# LitVP-V3.net
KiCad netlist of a schematic drawn in Altium Designer
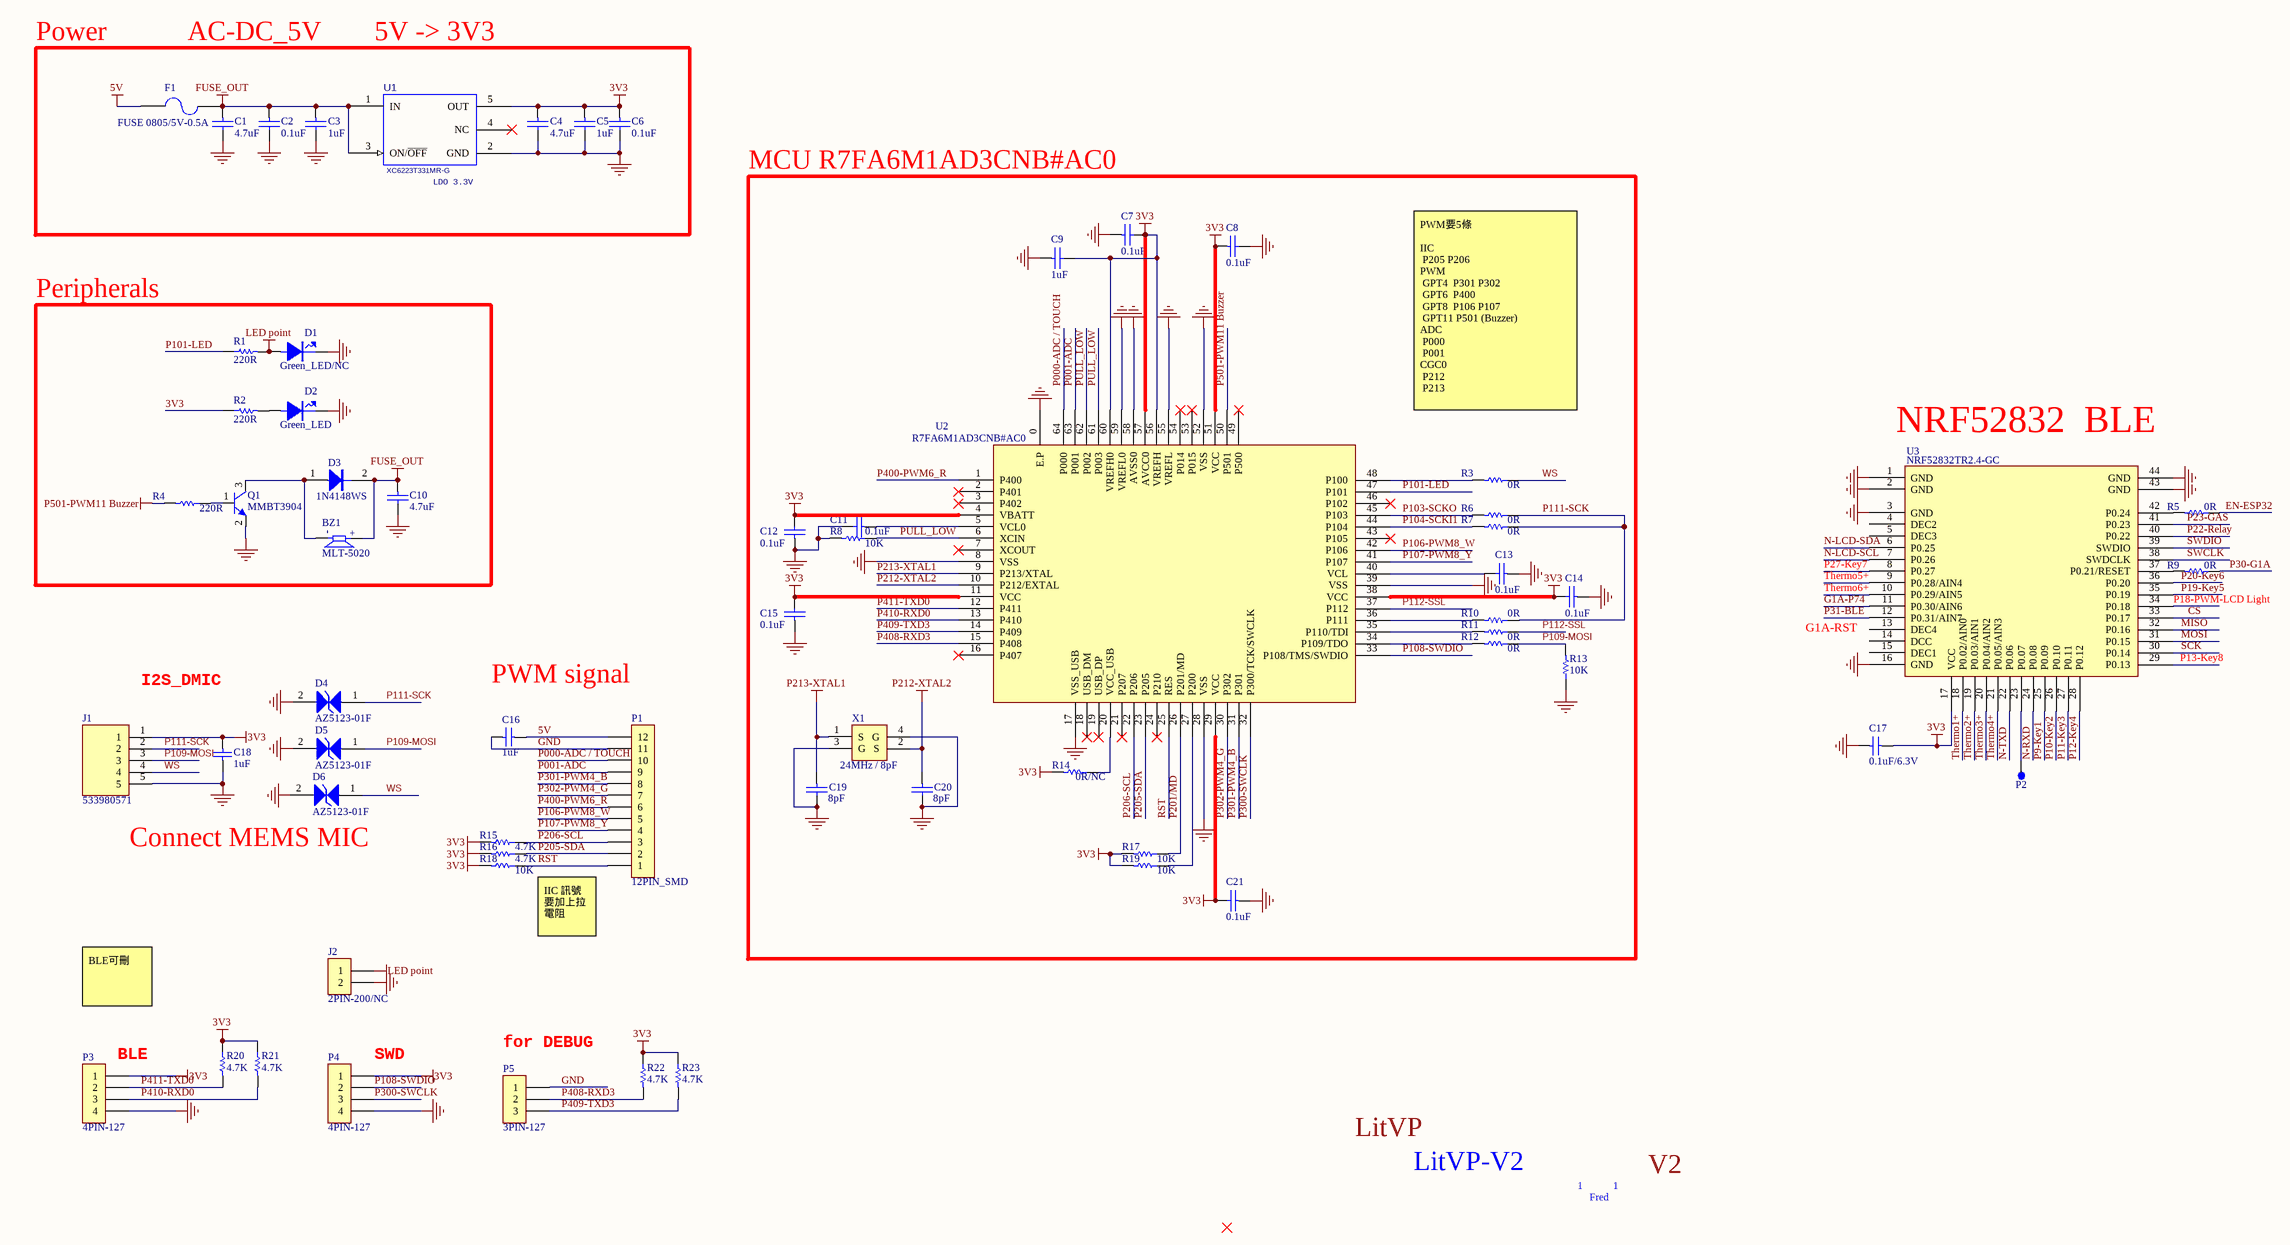
[diagram p0: LitVP-V3.SchDoc]

(export (version "E")
  (design (tool "Eeschema 10.0.6"))
  (components
    (comp (ref "BZ1")
      (value "MLT-5020")
      (footprint "BUZZER-SMD-5*5mm")
      (description "Buzzer")
      (libsource (lib "*") (part "YZ5020CS-03L-4.0-12-R"))
    )
    (comp (ref "C1")
      (value "4.7uF")
      (footprint "QUAN:0402C")
      (description "Capacitor")
      (libsource (lib "CAP") (part "CAP"))
    )
    (comp (ref "C2")
      (value "0.1uF")
      (footprint "QUAN:0402C")
      (description "Capacitor")
      (libsource (lib "CAP") (part "CAP"))
    )
    (comp (ref "C3")
      (value "1uF")
      (footprint "QUAN:0402C")
      (description "Capacitor")
      (libsource (lib "CAP") (part "CAP"))
    )
    (comp (ref "C4")
      (value "4.7uF")
      (footprint "QUAN:0402C")
      (description "Capacitor")
      (libsource (lib "CAP") (part "CAP"))
    )
    (comp (ref "C5")
      (value "1uF")
      (footprint "QUAN:0402C")
      (description "Capacitor")
      (libsource (lib "CAP") (part "CAP"))
    )
    (comp (ref "C6")
      (value "0.1uF")
      (footprint "QUAN:0402C")
      (description "Capacitor")
      (libsource (lib "CAP") (part "CAP"))
    )
    (comp (ref "C7")
      (value "0.1uF")
      (footprint "QUAN:0402C")
      (description "Capacitor")
      (libsource (lib "CAP") (part "CAP"))
    )
    (comp (ref "C8")
      (value "0.1uF")
      (footprint "QUAN:0402C")
      (description "Capacitor")
      (libsource (lib "CAP") (part "CAP"))
    )
    (comp (ref "C9")
      (value "1uF")
      (footprint "QUAN:0402C")
      (description "Capacitor")
      (libsource (lib "CAP") (part "CAP"))
    )
    (comp (ref "C10")
      (value "4.7uF")
      (footprint "QUAN:0402C")
      (description "Capacitor")
      (libsource (lib "CAP") (part "CAP"))
    )
    (comp (ref "C11")
      (value "0.1uF")
      (footprint "QUAN:0402C")
      (description "Capacitor")
      (libsource (lib "CAP") (part "CAP"))
    )
    (comp (ref "C12")
      (value "0.1uF")
      (footprint "QUAN:0402C")
      (description "Capacitor")
      (libsource (lib "CAP") (part "CAP"))
    )
    (comp (ref "C13")
      (value "0.1uF")
      (footprint "QUAN:0402C")
      (description "Capacitor")
      (libsource (lib "CAP") (part "CAP"))
    )
    (comp (ref "C14")
      (value "0.1uF")
      (footprint "QUAN:0402C")
      (description "Capacitor")
      (libsource (lib "CAP") (part "CAP"))
    )
    (comp (ref "C15")
      (value "0.1uF")
      (footprint "QUAN:0402C")
      (description "Capacitor")
      (libsource (lib "CAP") (part "CAP"))
    )
    (comp (ref "C16")
      (value "1uF")
      (footprint "QUAN:0402C")
      (description "Capacitor")
      (libsource (lib "*") (part "Cap Semi"))
    )
    (comp (ref "C17")
      (value "0.1uF/6.3V")
      (footprint "0402C")
      (description "Capacitor (Semiconductor SIM Model)")
      (fields (field (name "PUBLISHER") "Altium Limited"))
      (libsource (lib "*") (part "Cap Semi"))
    )
    (comp (ref "C18")
      (value "1uF")
      (footprint "QUAN:0402C")
      (description "Capacitor")
      (libsource (lib "*") (part "Cap Semi"))
    )
    (comp (ref "C19")
      (value "8pF")
      (footprint "QUAN:0402C")
      (description "Capacitor")
      (libsource (lib "*") (part "CAP"))
    )
    (comp (ref "C20")
      (value "8pF")
      (footprint "QUAN:0402C")
      (description "Capacitor")
      (libsource (lib "*") (part "CAP"))
    )
    (comp (ref "C21")
      (value "0.1uF")
      (footprint "QUAN:0402C")
      (description "Capacitor")
      (libsource (lib "CAP") (part "CAP"))
    )
    (comp (ref "D1")
      (value "Green_LED/NC")
      (footprint "LED0603--0.4mm")
      (fields
        (field (name "MANUFACTURER'S PART NUMBER") "CL-170G-CD-T")
        (field (name "PART NUMBER") "41100017000")
        (field (name "MANUFACTURER") "Citizen")
      )
      (libsource (lib "*") (part "LED"))
    )
    (comp (ref "D2")
      (value "Green_LED")
      (footprint "LED0603--0.4mm")
      (fields
        (field (name "MANUFACTURER'S PART NUMBER") "CL-170G-CD-T")
        (field (name "PART NUMBER") "41100017000")
        (field (name "MANUFACTURER") "Citizen")
      )
      (libsource (lib "*") (part "LED"))
    )
    (comp (ref "D3")
      (value "1N4148WS")
      (footprint "SOD323-1N4148WS - pig pad")
      (libsource (lib "*") (part "DIODE"))
    )
    (comp (ref "D4")
      (value "AZ5123-01F")
      (footprint "LitVP-02:DIODE-0402")
      (description "ESD")
      (libsource (lib "*") (part "PESD5V0L1BA"))
    )
    (comp (ref "D5")
      (value "AZ5123-01F")
      (footprint "DIODE-0402")
      (description "ESD")
      (libsource (lib "*") (part "PESD5V0L1BA"))
    )
    (comp (ref "D6")
      (value "AZ5123-01F")
      (footprint "DIODE-0402")
      (description "ESD")
      (libsource (lib "*") (part "PESD5V0L1BA"))
    )
    (comp (ref "F1")
      (value "FUSE 0805/5V-0.5A")
      (footprint "QUAN:0805_FUSE")
      (description "Fuse")
      (libsource (lib "*") (part "FUSE2"))
    )
    (comp (ref "J1")
      (value "533980571")
      (footprint "SamacSys:53398-0571")
      (description "Connector")
      (fields (field (name "MANUFACTURER_PART_NUMBER") "53048-0510"))
      (libsource (lib "*") (part "53048-0510"))
    )
    (comp (ref "J2")
      (value "2PIN-200/NC")
      (footprint "2PIN-127")
      (description "Connector")
      (libsource (lib "PIN") (part "2PIN-200"))
    )
    (comp (ref "P1")
      (value "12PIN_SMD")
      (footprint "QUAN:12PIN_SAMTEC-MMT-136-02-X-SH")
      (libsource (lib "PIN") (part "12PIN_SMD"))
    )
    (comp (ref "P2") (value "TP") (footprint "TESTPAD-1X0.6MM-1") (libsource (lib "*") (part "TP")))
    (comp (ref "P3")
      (value "4PIN-127")
      (footprint "QUAN:4PIN-127_0.85_0.505")
      (description "1.27mm Header")
      (libsource (lib "*") (part "CON4"))
    )
    (comp (ref "P4")
      (value "4PIN-127")
      (footprint "QUAN:4PIN-127_0.85_0.505")
      (description "1.27mm Header")
      (libsource (lib "*") (part "CON4"))
    )
    (comp (ref "P5") (value "3PIN-127") (footprint "QUAN:3PIN-127") (libsource (lib "PIN") (part "3PIN-127")))
    (comp (ref "Q1")
      (value "MMBT3904")
      (footprint "QUAN:SOT-23")
      (description "NPN General Purpose Amplifier")
      (fields (field (name "PUBLISHER") "*"))
      (libsource (lib "*") (part "NPN-3"))
    )
    (comp (ref "R1")
      (value "220R")
      (footprint "QUAN:0402")
      (description "Resistor")
      (libsource (lib "*") (part "Res Semi"))
    )
    (comp (ref "R2")
      (value "220R")
      (footprint "QUAN:0402")
      (description "Resistor")
      (libsource (lib "*") (part "Res Semi"))
    )
    (comp (ref "R3")
      (value "0R")
      (footprint "QUAN:0402")
      (description "Resistor")
      (libsource (lib "*") (part "Res Semi"))
    )
    (comp (ref "R4")
      (value "220R")
      (footprint "QUAN:0402")
      (description "Resistor")
      (libsource (lib "*") (part "Res Semi"))
    )
    (comp (ref "R5")
      (value "0R")
      (footprint "0402")
      (description "Semiconductor Resistor")
      (fields (field (name "PUBLISHER") "Altium Limited"))
      (libsource (lib "*") (part "Res Semi"))
    )
    (comp (ref "R6")
      (value "0R")
      (footprint "QUAN:0402")
      (description "Resistor")
      (libsource (lib "*") (part "Res Semi"))
    )
    (comp (ref "R7")
      (value "0R")
      (footprint "QUAN:0402")
      (description "Resistor")
      (libsource (lib "*") (part "Res Semi"))
    )
    (comp (ref "R8")
      (value "10K")
      (footprint "QUAN:0402")
      (description "Resistor")
      (libsource (lib "*") (part "Res Semi"))
    )
    (comp (ref "R9")
      (value "0R")
      (footprint "0402")
      (description "Semiconductor Resistor")
      (fields (field (name "PUBLISHER") "Altium Limited"))
      (libsource (lib "*") (part "Res Semi"))
    )
    (comp (ref "R10")
      (value "0R")
      (footprint "QUAN:0402")
      (description "Resistor")
      (libsource (lib "*") (part "Res Semi"))
    )
    (comp (ref "R11")
      (value "0R")
      (footprint "QUAN:0402")
      (description "Resistor")
      (libsource (lib "*") (part "Res Semi"))
    )
    (comp (ref "R12")
      (value "0R")
      (footprint "QUAN:0402")
      (description "Resistor")
      (libsource (lib "*") (part "Res Semi"))
    )
    (comp (ref "R13")
      (value "10K")
      (footprint "QUAN:0402")
      (description "Resistor")
      (libsource (lib "*") (part "Res Semi"))
    )
    (comp (ref "R14")
      (value "0R/NC")
      (footprint "QUAN:0402")
      (description "Resistor")
      (libsource (lib "*") (part "Res Semi"))
    )
    (comp (ref "R15")
      (value "4.7K")
      (footprint "QUAN:0402")
      (description "Resistor")
      (libsource (lib "*") (part "Res Semi"))
    )
    (comp (ref "R16")
      (value "4.7K")
      (footprint "QUAN:0402")
      (description "Resistor")
      (libsource (lib "*") (part "Res Semi"))
    )
    (comp (ref "R17")
      (value "10K")
      (footprint "QUAN:0402")
      (description "Resistor")
      (libsource (lib "*") (part "Res Semi"))
    )
    (comp (ref "R18")
      (value "10K")
      (footprint "QUAN:0402")
      (description "Resistor")
      (libsource (lib "*") (part "Res Semi"))
    )
    (comp (ref "R19")
      (value "10K")
      (footprint "QUAN:0402")
      (description "Resistor")
      (libsource (lib "*") (part "Res Semi"))
    )
    (comp (ref "R20")
      (value "4.7K")
      (footprint "QUAN:0402")
      (description "Resistor")
      (libsource (lib "*") (part "Res Semi"))
    )
    (comp (ref "R21")
      (value "4.7K")
      (footprint "QUAN:0402")
      (description "Resistor")
      (libsource (lib "*") (part "Res Semi"))
    )
    (comp (ref "R22")
      (value "4.7K")
      (footprint "QUAN:0402")
      (description "Resistor")
      (libsource (lib "*") (part "Res Semi"))
    )
    (comp (ref "R23")
      (value "4.7K")
      (footprint "QUAN:0402")
      (description "Resistor")
      (libsource (lib "*") (part "Res Semi"))
    )
    (comp (ref "U1")
      (value "XC6223T331MR-G")
      (footprint "SOT-23-5-0.95MM")
      (libsource (lib "*") (part "XC6223T331MR-G"))
    )
    (comp (ref "U2")
      (value "R7FA6M1AD3CNB#AC0")
      (footprint "QFN64-0.4mm-8X8")
      (description "MCU")
      (libsource (lib "*") (part "R7FA6M1AD3CNB#AC0"))
    )
    (comp (ref "U3")
      (value "NRF52832TR2.4-GC")
      (footprint "NRF52832TR2.4-GC")
      (libsource (lib "*") (part "NRF52832TR2.4-GC"))
    )
    (comp (ref "X1")
      (value "24MHz / 8pF")
      (footprint "XTAL-SMD-20X16")
      (libsource (lib "*") (part "XTAL-SMD-25*32"))
    )
  )
  (nets
    (net (code "1") (name "/CS") (class "Default")
      (node (ref "U3") (pin "33") (pinfunction "P0.17_33") (pintype "passive"))
    )
    (net (code "2") (name "/EN-ESP32") (class "Default")
      (node (ref "R5") (pin "1") (pinfunction "1_1") (pintype "passive"))
    )
    (net (code "3") (name "/G1A-P74") (class "Default")
      (node (ref "U3") (pin "11") (pinfunction "P0.30/AIN6_11") (pintype "passive"))
    )
    (net (code "4") (name "/MISO") (class "Default")
      (node (ref "U3") (pin "32") (pinfunction "P0.16_32") (pintype "passive"))
    )
    (net (code "5") (name "/MOSI") (class "Default")
      (node (ref "U3") (pin "31") (pinfunction "P0.15_31") (pintype "passive"))
    )
    (net (code "6") (name "/N-LCD-SCL") (class "Default")
      (node (ref "U3") (pin "7") (pinfunction "P0.26_7") (pintype "passive"))
    )
    (net (code "7") (name "/N-LCD-SDA") (class "Default")
      (node (ref "U3") (pin "6") (pinfunction "P0.25_6") (pintype "passive"))
    )
    (net (code "8") (name "/N-RXD") (class "Default")
      (node (ref "U3") (pin "24") (pinfunction "P0.08_24") (pintype "passive"))
    )
    (net (code "9") (name "/N-TXD") (class "Default")
      (node (ref "U3") (pin "22") (pinfunction "P0.06_22") (pintype "passive"))
    )
    (net (code "10") (name "/P000-ADC {slash} TOUCH") (class "Default")
      (node (ref "P1") (pin "10") (pinfunction "10_10") (pintype "passive"))
      (node (ref "U2") (pin "64") (pinfunction "P000_64") (pintype "passive"))
    )
    (net (code "11") (name "/P001-ADC") (class "Default")
      (node (ref "P1") (pin "9") (pinfunction "9_9") (pintype "passive"))
      (node (ref "U2") (pin "63") (pinfunction "P001_63") (pintype "passive"))
    )
    (net (code "12") (name "/P9-Key1") (class "Default")
      (node (ref "U3") (pin "25") (pinfunction "P0.09_25") (pintype "passive"))
    )
    (net (code "13") (name "/P10-Key2") (class "Default")
      (node (ref "U3") (pin "26") (pinfunction "P0.10_26") (pintype "passive"))
    )
    (net (code "14") (name "/P11-Key3") (class "Default")
      (node (ref "U3") (pin "27") (pinfunction "P0.11_27") (pintype "passive"))
    )
    (net (code "15") (name "/P12-Key4") (class "Default")
      (node (ref "U3") (pin "28") (pinfunction "P0.12_28") (pintype "passive"))
    )
    (net (code "16") (name "/P13-Key8") (class "Default")
      (node (ref "U3") (pin "29") (pinfunction "P0.13_29") (pintype "passive"))
    )
    (net (code "17") (name "/P18-PWM-LCD Light") (class "Default")
      (node (ref "U3") (pin "34") (pinfunction "P0.18_34") (pintype "passive"))
    )
    (net (code "18") (name "/P19-Key5") (class "Default")
      (node (ref "U3") (pin "35") (pinfunction "P0.19_35") (pintype "passive"))
    )
    (net (code "19") (name "/P20-Key6") (class "Default")
      (node (ref "U3") (pin "36") (pinfunction "P0.20_36") (pintype "passive"))
    )
    (net (code "20") (name "/P22-Relay") (class "Default")
      (node (ref "U3") (pin "40") (pinfunction "P0.22_40") (pintype "passive"))
    )
    (net (code "21") (name "/P23-GAS") (class "Default")
      (node (ref "U3") (pin "41") (pinfunction "P0.23_41") (pintype "passive"))
    )
    (net (code "22") (name "/P27-Key7") (class "Default")
      (node (ref "U3") (pin "8") (pinfunction "P0.27_8") (pintype "passive"))
    )
    (net (code "23") (name "/P30-G1A") (class "Default")
      (node (ref "R9") (pin "1") (pinfunction "1_1") (pintype "passive"))
    )
    (net (code "24") (name "/P31-BLE") (class "Default")
      (node (ref "U3") (pin "12") (pinfunction "P0.31/AIN7_12") (pintype "passive"))
    )
    (net (code "25") (name "/P101-LED") (class "Default")
      (node (ref "R1") (pin "1") (pinfunction "1_1") (pintype "passive"))
      (node (ref "U2") (pin "47") (pinfunction "P101_47") (pintype "passive"))
    )
    (net (code "26") (name "/P103-SCKO") (class "Default")
      (node (ref "R6") (pin "2") (pinfunction "2_2") (pintype "passive"))
      (node (ref "U2") (pin "45") (pinfunction "P103_45") (pintype "passive"))
    )
    (net (code "27") (name "/P104-SCKI1") (class "Default")
      (node (ref "R7") (pin "2") (pinfunction "2_2") (pintype "passive"))
      (node (ref "U2") (pin "44") (pinfunction "P104_44") (pintype "passive"))
    )
    (net (code "28") (name "/P106-PWM8_W") (class "Default")
      (node (ref "P1") (pin "5") (pinfunction "5_5") (pintype "passive"))
      (node (ref "U2") (pin "42") (pinfunction "P106_42") (pintype "passive"))
    )
    (net (code "29") (name "/P107-PWM8_Y") (class "Default")
      (node (ref "P1") (pin "4") (pinfunction "4_4") (pintype "passive"))
      (node (ref "U2") (pin "41") (pinfunction "P107_41") (pintype "passive"))
    )
    (net (code "30") (name "/P108-SWDIO") (class "Default")
      (node (ref "P4") (pin "2") (pinfunction "2_2") (pintype "passive"))
      (node (ref "U2") (pin "33") (pinfunction "P108/TMS/SWDIO_33") (pintype "passive"))
    )
    (net (code "31") (name "/P109-MOSI") (class "Default")
      (node (ref "D5") (pin "1") (pinfunction "1_1") (pintype "passive"))
      (node (ref "J1") (pin "3") (pinfunction "3_3") (pintype "passive"))
      (node (ref "R12") (pin "1") (pinfunction "1_1") (pintype "passive"))
      (node (ref "R13") (pin "2") (pinfunction "2_2") (pintype "passive"))
    )
    (net (code "32") (name "/P111-SCK") (class "Default")
      (node (ref "D4") (pin "1") (pinfunction "1_1") (pintype "passive"))
      (node (ref "J1") (pin "2") (pinfunction "2_2") (pintype "passive"))
      (node (ref "R10") (pin "1") (pinfunction "1_1") (pintype "passive"))
      (node (ref "R6") (pin "1") (pinfunction "1_1") (pintype "passive"))
      (node (ref "R7") (pin "1") (pinfunction "1_1") (pintype "passive"))
    )
    (net (code "33") (name "/P112-SSL") (class "Default")
      (node (ref "R11") (pin "1") (pinfunction "1_1") (pintype "passive"))
      (node (ref "U2") (pin "37") (pinfunction "P112_37") (pintype "passive"))
    )
    (net (code "34") (name "/P201{slash}MD") (class "Default")
      (node (ref "R17") (pin "1") (pinfunction "1_1") (pintype "passive"))
      (node (ref "U2") (pin "26") (pinfunction "P201/MD_26") (pintype "passive"))
    )
    (net (code "35") (name "/P205-SDA") (class "Default")
      (node (ref "P1") (pin "2") (pinfunction "2_2") (pintype "passive"))
      (node (ref "R16") (pin "1") (pinfunction "1_1") (pintype "passive"))
      (node (ref "U2") (pin "23") (pinfunction "P205_23") (pintype "passive"))
    )
    (net (code "36") (name "/P206-SCL") (class "Default")
      (node (ref "P1") (pin "3") (pinfunction "3_3") (pintype "passive"))
      (node (ref "R15") (pin "1") (pinfunction "1_1") (pintype "passive"))
      (node (ref "U2") (pin "22") (pinfunction "P206_22") (pintype "passive"))
    )
    (net (code "37") (name "/P300-SWCLK") (class "Default")
      (node (ref "P4") (pin "3") (pinfunction "3_3") (pintype "passive"))
      (node (ref "U2") (pin "32") (pinfunction "P300/TCK/SWCLK_32") (pintype "passive"))
    )
    (net (code "38") (name "/P301-PWM4_B") (class "Default")
      (node (ref "P1") (pin "8") (pinfunction "8_8") (pintype "passive"))
      (node (ref "U2") (pin "31") (pinfunction "P301_31") (pintype "passive"))
    )
    (net (code "39") (name "/P302-PWM4_G") (class "Default")
      (node (ref "P1") (pin "7") (pinfunction "7_7") (pintype "passive"))
      (node (ref "U2") (pin "30") (pinfunction "P302_30") (pintype "passive"))
    )
    (net (code "40") (name "/P400-PWM6_R") (class "Default")
      (node (ref "P1") (pin "6") (pinfunction "6_6") (pintype "passive"))
      (node (ref "U2") (pin "1") (pinfunction "P400_1") (pintype "passive"))
    )
    (net (code "41") (name "/P408-RXD3") (class "Default")
      (node (ref "P5") (pin "2") (pinfunction "2_2") (pintype "passive"))
      (node (ref "R22") (pin "2") (pinfunction "2_2") (pintype "passive"))
      (node (ref "U2") (pin "15") (pinfunction "P408_15") (pintype "passive"))
    )
    (net (code "42") (name "/P409-TXD3") (class "Default")
      (node (ref "P5") (pin "3") (pinfunction "3_3") (pintype "passive"))
      (node (ref "R23") (pin "2") (pinfunction "2_2") (pintype "passive"))
      (node (ref "U2") (pin "14") (pinfunction "P409_14") (pintype "passive"))
    )
    (net (code "43") (name "/P410-RXD0") (class "Default")
      (node (ref "P3") (pin "3") (pinfunction "3_3") (pintype "passive"))
      (node (ref "R21") (pin "2") (pinfunction "2_2") (pintype "passive"))
      (node (ref "U2") (pin "13") (pinfunction "P410_13") (pintype "passive"))
    )
    (net (code "44") (name "/P411-TXD0") (class "Default")
      (node (ref "P3") (pin "2") (pinfunction "2_2") (pintype "passive"))
      (node (ref "R20") (pin "2") (pinfunction "2_2") (pintype "passive"))
      (node (ref "U2") (pin "12") (pinfunction "P411_12") (pintype "passive"))
    )
    (net (code "45") (name "/PULL_LOW") (class "Default")
      (node (ref "R8") (pin "1") (pinfunction "1_1") (pintype "passive"))
      (node (ref "U2") (pin "6") (pinfunction "XCIN_6") (pintype "passive"))
      (node (ref "U2") (pin "61") (pinfunction "P003_61") (pintype "passive"))
      (node (ref "U2") (pin "62") (pinfunction "P002_62") (pintype "passive"))
    )
    (net (code "46") (name "/RST") (class "Default")
      (node (ref "P1") (pin "1") (pinfunction "1_1") (pintype "passive"))
      (node (ref "R18") (pin "1") (pinfunction "1_1") (pintype "passive"))
      (node (ref "U2") (pin "25") (pinfunction "RES_25") (pintype "passive"))
    )
    (net (code "47") (name "/SCK") (class "Default")
      (node (ref "U3") (pin "30") (pinfunction "P0.14_30") (pintype "passive"))
    )
    (net (code "48") (name "/SWCLK") (class "Default")
      (node (ref "U3") (pin "38") (pinfunction "SWDCLK_38") (pintype "passive"))
    )
    (net (code "49") (name "/SWDIO") (class "Default")
      (node (ref "U3") (pin "39") (pinfunction "SWDIO_39") (pintype "passive"))
    )
    (net (code "50") (name "/Thermo1+") (class "Default")
      (node (ref "U3") (pin "18") (pinfunction "P0.02/AIN0_18") (pintype "passive"))
    )
    (net (code "51") (name "/Thermo2+") (class "Default")
      (node (ref "U3") (pin "19") (pinfunction "P0.03/AIN1_19") (pintype "passive"))
    )
    (net (code "52") (name "/Thermo3+") (class "Default")
      (node (ref "U3") (pin "20") (pinfunction "P0.04/AIN2_20") (pintype "passive"))
    )
    (net (code "53") (name "/Thermo4+") (class "Default")
      (node (ref "U3") (pin "21") (pinfunction "P0.05/AIN3_21") (pintype "passive"))
    )
    (net (code "54") (name "/Thermo5+") (class "Default")
      (node (ref "U3") (pin "9") (pinfunction "P0.28/AIN4_9") (pintype "passive"))
    )
    (net (code "55") (name "/Thermo6+") (class "Default")
      (node (ref "U3") (pin "10") (pinfunction "P0.29/AIN5_10") (pintype "passive"))
    )
    (net (code "56") (name "/WS") (class "Default")
      (node (ref "D6") (pin "1") (pinfunction "1_1") (pintype "passive"))
      (node (ref "J1") (pin "4") (pinfunction "4_4") (pintype "passive"))
      (node (ref "R3") (pin "1") (pinfunction "1_1") (pintype "passive"))
    )
    (net (code "57") (name "3V3") (class "Default")
      (node (ref "C12") (pin "2") (pinfunction "2_2") (pintype "passive"))
      (node (ref "C14") (pin "2") (pinfunction "2_2") (pintype "passive"))
      (node (ref "C15") (pin "2") (pinfunction "2_2") (pintype "passive"))
      (node (ref "C17") (pin "1") (pinfunction "1_1") (pintype "passive"))
      (node (ref "C18") (pin "2") (pinfunction "2_2") (pintype "passive"))
      (node (ref "C21") (pin "2") (pinfunction "2_2") (pintype "passive"))
      (node (ref "C4") (pin "1") (pinfunction "1_1") (pintype "passive"))
      (node (ref "C5") (pin "1") (pinfunction "1_1") (pintype "passive"))
      (node (ref "C6") (pin "1") (pinfunction "1_1") (pintype "passive"))
      (node (ref "C7") (pin "2") (pinfunction "2_2") (pintype "passive"))
      (node (ref "C8") (pin "1") (pinfunction "1_1") (pintype "passive"))
      (node (ref "C9") (pin "2") (pinfunction "2_2") (pintype "passive"))
      (node (ref "J1") (pin "1") (pinfunction "1_1") (pintype "passive"))
      (node (ref "P3") (pin "1") (pinfunction "1_1") (pintype "passive"))
      (node (ref "P4") (pin "1") (pinfunction "1_1") (pintype "passive"))
      (node (ref "R14") (pin "2") (pinfunction "2_2") (pintype "passive"))
      (node (ref "R15") (pin "2") (pinfunction "2_2") (pintype "passive"))
      (node (ref "R16") (pin "2") (pinfunction "2_2") (pintype "passive"))
      (node (ref "R17") (pin "2") (pinfunction "2_2") (pintype "passive"))
      (node (ref "R18") (pin "2") (pinfunction "2_2") (pintype "passive"))
      (node (ref "R19") (pin "2") (pinfunction "2_2") (pintype "passive"))
      (node (ref "R2") (pin "1") (pinfunction "1_1") (pintype "passive"))
      (node (ref "R20") (pin "1") (pinfunction "1_1") (pintype "passive"))
      (node (ref "R21") (pin "1") (pinfunction "1_1") (pintype "passive"))
      (node (ref "R22") (pin "1") (pinfunction "1_1") (pintype "passive"))
      (node (ref "R23") (pin "1") (pinfunction "1_1") (pintype "passive"))
      (node (ref "U1") (pin "5") (pinfunction "OUT_5") (pintype "passive"))
      (node (ref "U2") (pin "11") (pinfunction "VCC_11") (pintype "passive"))
      (node (ref "U2") (pin "29") (pinfunction "VCC_29") (pintype "passive"))
      (node (ref "U2") (pin "38") (pinfunction "VCC_38") (pintype "passive"))
      (node (ref "U2") (pin "4") (pinfunction "VBATT_4") (pintype "passive"))
      (node (ref "U2") (pin "51") (pinfunction "VCC_51") (pintype "passive"))
      (node (ref "U2") (pin "56") (pinfunction "VREFH_56") (pintype "passive"))
      (node (ref "U2") (pin "57") (pinfunction "AVCC0_57") (pintype "passive"))
      (node (ref "U2") (pin "60") (pinfunction "VREFH0_60") (pintype "passive"))
      (node (ref "U3") (pin "17") (pinfunction "VCC_17") (pintype "passive"))
    )
    (net (code "58") (name "5V") (class "Default")
      (node (ref "C16") (pin "1") (pinfunction "1_1") (pintype "passive"))
      (node (ref "F1") (pin "1") (pinfunction "1_1") (pintype "passive"))
      (node (ref "P1") (pin "12") (pinfunction "12_12") (pintype "passive"))
    )
    (net (code "59") (name "FUSE_OUT") (class "Default")
      (node (ref "BZ1") (pin "1") (pinfunction "1_1") (pintype "passive"))
      (node (ref "C1") (pin "1") (pinfunction "1_1") (pintype "passive"))
      (node (ref "C10") (pin "1") (pinfunction "1_1") (pintype "passive"))
      (node (ref "C2") (pin "1") (pinfunction "1_1") (pintype "passive"))
      (node (ref "C3") (pin "1") (pinfunction "1_1") (pintype "passive"))
      (node (ref "D3") (pin "2") (pinfunction "2_2") (pintype "passive"))
      (node (ref "F1") (pin "2") (pinfunction "2_2") (pintype "passive"))
      (node (ref "U1") (pin "1") (pinfunction "IN_1") (pintype "passive"))
      (node (ref "U1") (pin "3") (pinfunction "ON/~{OFF}_3") (pintype "input"))
    )
    (net (code "60") (name "GND") (class "Default")
      (node (ref "C1") (pin "2") (pinfunction "2_2") (pintype "passive"))
      (node (ref "C10") (pin "2") (pinfunction "2_2") (pintype "passive"))
      (node (ref "C11") (pin "2") (pinfunction "2_2") (pintype "passive"))
      (node (ref "C12") (pin "1") (pinfunction "1_1") (pintype "passive"))
      (node (ref "C13") (pin "1") (pinfunction "1_1") (pintype "passive"))
      (node (ref "C14") (pin "1") (pinfunction "1_1") (pintype "passive"))
      (node (ref "C15") (pin "1") (pinfunction "1_1") (pintype "passive"))
      (node (ref "C16") (pin "2") (pinfunction "2_2") (pintype "passive"))
      (node (ref "C17") (pin "2") (pinfunction "2_2") (pintype "passive"))
      (node (ref "C18") (pin "1") (pinfunction "1_1") (pintype "passive"))
      (node (ref "C19") (pin "2") (pinfunction "2_2") (pintype "passive"))
      (node (ref "C2") (pin "2") (pinfunction "2_2") (pintype "passive"))
      (node (ref "C20") (pin "2") (pinfunction "2_2") (pintype "passive"))
      (node (ref "C21") (pin "1") (pinfunction "1_1") (pintype "passive"))
      (node (ref "C3") (pin "2") (pinfunction "2_2") (pintype "passive"))
      (node (ref "C4") (pin "2") (pinfunction "2_2") (pintype "passive"))
      (node (ref "C5") (pin "2") (pinfunction "2_2") (pintype "passive"))
      (node (ref "C6") (pin "2") (pinfunction "2_2") (pintype "passive"))
      (node (ref "C7") (pin "1") (pinfunction "1_1") (pintype "passive"))
      (node (ref "C8") (pin "2") (pinfunction "2_2") (pintype "passive"))
      (node (ref "C9") (pin "1") (pinfunction "1_1") (pintype "passive"))
      (node (ref "D1") (pin "2") (pinfunction "2_2") (pintype "passive"))
      (node (ref "D2") (pin "2") (pinfunction "2_2") (pintype "passive"))
      (node (ref "D4") (pin "2") (pinfunction "2_2") (pintype "passive"))
      (node (ref "D5") (pin "2") (pinfunction "2_2") (pintype "passive"))
      (node (ref "D6") (pin "2") (pinfunction "2_2") (pintype "passive"))
      (node (ref "J1") (pin "5") (pinfunction "5_5") (pintype "passive"))
      (node (ref "J2") (pin "2") (pinfunction "2_2") (pintype "passive"))
      (node (ref "P1") (pin "11") (pinfunction "11_11") (pintype "passive"))
      (node (ref "P3") (pin "4") (pinfunction "4_4") (pintype "passive"))
      (node (ref "P4") (pin "4") (pinfunction "4_4") (pintype "passive"))
      (node (ref "P5") (pin "1") (pinfunction "1_1") (pintype "passive"))
      (node (ref "Q1") (pin "2") (pinfunction "E_2") (pintype "passive"))
      (node (ref "R13") (pin "1") (pinfunction "1_1") (pintype "passive"))
      (node (ref "R8") (pin "2") (pinfunction "2_2") (pintype "passive"))
      (node (ref "U1") (pin "2") (pinfunction "GND_2") (pintype "passive"))
      (node (ref "U2") (pin "0") (pinfunction "E.P_0") (pintype "passive"))
      (node (ref "U2") (pin "17") (pinfunction "VSS_USB_17") (pintype "passive"))
      (node (ref "U2") (pin "28") (pinfunction "VSS_28") (pintype "passive"))
      (node (ref "U2") (pin "39") (pinfunction "VSS_39") (pintype "passive"))
      (node (ref "U2") (pin "52") (pinfunction "VSS_52") (pintype "passive"))
      (node (ref "U2") (pin "55") (pinfunction "VREFL_55") (pintype "passive"))
      (node (ref "U2") (pin "58") (pinfunction "AVSS0_58") (pintype "passive"))
      (node (ref "U2") (pin "59") (pinfunction "VREFL0_59") (pintype "passive"))
      (node (ref "U2") (pin "8") (pinfunction "VSS_8") (pintype "passive"))
      (node (ref "U3") (pin "1") (pinfunction "GND_1") (pintype "passive"))
      (node (ref "U3") (pin "16") (pinfunction "GND_16") (pintype "passive"))
      (node (ref "U3") (pin "2") (pinfunction "GND_2") (pintype "passive"))
      (node (ref "U3") (pin "3") (pinfunction "GND_3") (pintype "passive"))
      (node (ref "U3") (pin "43") (pinfunction "GND_43") (pintype "passive"))
      (node (ref "U3") (pin "44") (pinfunction "GND_44") (pintype "passive"))
      (node (ref "X1") (pin "3") (pinfunction "G_3") (pintype "passive"))
      (node (ref "X1") (pin "4") (pinfunction "G_4") (pintype "passive"))
    )
    (net (code "61") (name "LED point") (class "Default")
      (node (ref "D1") (pin "1") (pinfunction "1_1") (pintype "passive"))
      (node (ref "J2") (pin "1") (pinfunction "1_1") (pintype "passive"))
      (node (ref "R1") (pin "2") (pinfunction "2_2") (pintype "passive"))
    )
    (net (code "62") (name "Net-(D2-Pad1)") (class "Default")
      (node (ref "D2") (pin "1") (pinfunction "1_1") (pintype "passive"))
      (node (ref "R2") (pin "2") (pinfunction "2_2") (pintype "passive"))
    )
    (net (code "63") (name "Net-(Q1-B)") (class "Default")
      (node (ref "Q1") (pin "1") (pinfunction "B_1") (pintype "passive"))
      (node (ref "R4") (pin "1") (pinfunction "1_1") (pintype "passive"))
    )
    (net (code "64") (name "Net-(Q1-C)") (class "Default")
      (node (ref "BZ1") (pin "2") (pinfunction "2_2") (pintype "passive"))
      (node (ref "D3") (pin "1") (pinfunction "1_1") (pintype "passive"))
      (node (ref "Q1") (pin "3") (pinfunction "C_3") (pintype "passive"))
    )
    (net (code "65") (name "Net-(U2-P100)") (class "Default")
      (node (ref "R3") (pin "2") (pinfunction "2_2") (pintype "passive"))
      (node (ref "U2") (pin "48") (pinfunction "P100_48") (pintype "passive"))
    )
    (net (code "66") (name "Net-(U2-P109{slash}TDO)") (class "Default")
      (node (ref "R12") (pin "2") (pinfunction "2_2") (pintype "passive"))
      (node (ref "U2") (pin "34") (pinfunction "P109/TDO_34") (pintype "passive"))
    )
    (net (code "67") (name "Net-(U2-P110{slash}TDI)") (class "Default")
      (node (ref "R11") (pin "2") (pinfunction "2_2") (pintype "passive"))
      (node (ref "U2") (pin "35") (pinfunction "P110/TDI_35") (pintype "passive"))
    )
    (net (code "68") (name "Net-(U2-P111)") (class "Default")
      (node (ref "R10") (pin "2") (pinfunction "2_2") (pintype "passive"))
      (node (ref "U2") (pin "36") (pinfunction "P111_36") (pintype "passive"))
    )
    (net (code "69") (name "Net-(U2-P200)") (class "Default")
      (node (ref "R19") (pin "1") (pinfunction "1_1") (pintype "passive"))
      (node (ref "U2") (pin "27") (pinfunction "P200_27") (pintype "passive"))
    )
    (net (code "70") (name "Net-(U2-VCC_USB)") (class "Default")
      (node (ref "R14") (pin "1") (pinfunction "1_1") (pintype "passive"))
      (node (ref "U2") (pin "20") (pinfunction "VCC_USB_20") (pintype "passive"))
    )
    (net (code "71") (name "Net-(U2-VCL)") (class "Default")
      (node (ref "C13") (pin "2") (pinfunction "2_2") (pintype "passive"))
      (node (ref "U2") (pin "40") (pinfunction "VCL_40") (pintype "passive"))
    )
    (net (code "72") (name "Net-(U2-VCL0)") (class "Default")
      (node (ref "C11") (pin "1") (pinfunction "1_1") (pintype "passive"))
      (node (ref "U2") (pin "5") (pinfunction "VCL0_5") (pintype "passive"))
    )
    (net (code "73") (name "Net-(U3-P0.07)") (class "Default")
      (node (ref "P2") (pin "1") (pinfunction "1_1") (pintype "passive"))
      (node (ref "U3") (pin "23") (pinfunction "P0.07_23") (pintype "passive"))
    )
    (net (code "74") (name "Net-(U3-P0.21{slash}RESET)") (class "Default")
      (node (ref "R9") (pin "2") (pinfunction "2_2") (pintype "passive"))
      (node (ref "U3") (pin "37") (pinfunction "P0.21/RESET_37") (pintype "passive"))
    )
    (net (code "75") (name "Net-(U3-P0.24)") (class "Default")
      (node (ref "R5") (pin "2") (pinfunction "2_2") (pintype "passive"))
      (node (ref "U3") (pin "42") (pinfunction "P0.24_42") (pintype "passive"))
    )
    (net (code "76") (name "P212-XTAL2") (class "Default")
      (node (ref "C20") (pin "1") (pinfunction "1_1") (pintype "passive"))
      (node (ref "U2") (pin "10") (pinfunction "P212/EXTAL_10") (pintype "passive"))
      (node (ref "X1") (pin "2") (pinfunction "S_2") (pintype "passive"))
    )
    (net (code "77") (name "P213-XTAL1") (class "Default")
      (node (ref "C19") (pin "1") (pinfunction "1_1") (pintype "passive"))
      (node (ref "U2") (pin "9") (pinfunction "P213/XTAL_9") (pintype "passive"))
      (node (ref "X1") (pin "1") (pinfunction "S_1") (pintype "passive"))
    )
    (net (code "78") (name "P501-PWM11 Buzzer") (class "Default")
      (node (ref "R4") (pin "2") (pinfunction "2_2") (pintype "passive"))
      (node (ref "U2") (pin "50") (pinfunction "P501_50") (pintype "passive"))
    )
    (net (code "79") (name "unconnected-(U1-NC-Pad4)") (class "Default")
      (node (ref "U1") (pin "4") (pinfunction "NC_4") (pintype "passive+no_connect"))
    )
    (net (code "80") (name "unconnected-(U2-P014-Pad54)") (class "Default")
      (node (ref "U2") (pin "54") (pinfunction "P014_54") (pintype "passive+no_connect"))
    )
    (net (code "81") (name "unconnected-(U2-P015-Pad53)") (class "Default")
      (node (ref "U2") (pin "53") (pinfunction "P015_53") (pintype "passive+no_connect"))
    )
    (net (code "82") (name "unconnected-(U2-P102-Pad46)") (class "Default")
      (node (ref "U2") (pin "46") (pinfunction "P102_46") (pintype "passive+no_connect"))
    )
    (net (code "83") (name "unconnected-(U2-P105-Pad43)") (class "Default")
      (node (ref "U2") (pin "43") (pinfunction "P105_43") (pintype "passive+no_connect"))
    )
    (net (code "84") (name "unconnected-(U2-P207-Pad21)") (class "Default")
      (node (ref "U2") (pin "21") (pinfunction "P207_21") (pintype "passive+no_connect"))
    )
    (net (code "85") (name "unconnected-(U2-P210-Pad24)") (class "Default")
      (node (ref "U2") (pin "24") (pinfunction "P210_24") (pintype "passive+no_connect"))
    )
    (net (code "86") (name "unconnected-(U2-P401-Pad2)") (class "Default")
      (node (ref "U2") (pin "2") (pinfunction "P401_2") (pintype "passive+no_connect"))
    )
    (net (code "87") (name "unconnected-(U2-P402-Pad3)") (class "Default")
      (node (ref "U2") (pin "3") (pinfunction "P402_3") (pintype "passive+no_connect"))
    )
    (net (code "88") (name "unconnected-(U2-P407-Pad16)") (class "Default")
      (node (ref "U2") (pin "16") (pinfunction "P407_16") (pintype "passive+no_connect"))
    )
    (net (code "89") (name "unconnected-(U2-P500-Pad49)") (class "Default")
      (node (ref "U2") (pin "49") (pinfunction "P500_49") (pintype "passive+no_connect"))
    )
    (net (code "90") (name "unconnected-(U2-USB_DM-Pad18)") (class "Default")
      (node (ref "U2") (pin "18") (pinfunction "USB_DM_18") (pintype "passive+no_connect"))
    )
    (net (code "91") (name "unconnected-(U2-USB_DP-Pad19)") (class "Default")
      (node (ref "U2") (pin "19") (pinfunction "USB_DP_19") (pintype "passive+no_connect"))
    )
    (net (code "92") (name "unconnected-(U2-XCOUT-Pad7)") (class "Default")
      (node (ref "U2") (pin "7") (pinfunction "XCOUT_7") (pintype "passive+no_connect"))
    )
    (net (code "93") (name "unconnected-(U3-DCC-Pad14)") (class "Default")
      (node (ref "U3") (pin "14") (pinfunction "DCC_14") (pintype "passive"))
    )
    (net (code "94") (name "unconnected-(U3-DEC1-Pad15)") (class "Default")
      (node (ref "U3") (pin "15") (pinfunction "DEC1_15") (pintype "passive"))
    )
    (net (code "95") (name "unconnected-(U3-DEC2-Pad4)") (class "Default")
      (node (ref "U3") (pin "4") (pinfunction "DEC2_4") (pintype "passive"))
    )
    (net (code "96") (name "unconnected-(U3-DEC3-Pad5)") (class "Default")
      (node (ref "U3") (pin "5") (pinfunction "DEC3_5") (pintype "passive"))
    )
    (net (code "97") (name "unconnected-(U3-DEC4-Pad13)") (class "Default")
      (node (ref "U3") (pin "13") (pinfunction "DEC4_13") (pintype "passive"))
    )
  )
)
